# 2uprava4.net
KiCad netlist of a schematic drawn in EAGLE
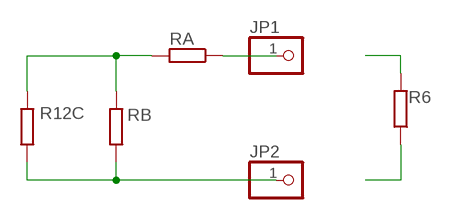
[diagram p0: schematic, sheet 1]

(export (version "E")
  (design (tool "Eeschema 10.0.6"))
  (components
    (comp (ref "JP1")
      (value "PINHD-1X1")
      (footprint "eagle-import:1X01")
      (libsource (lib "eagle-import") (part "PINHD-1X1"))
    )
    (comp (ref "JP2")
      (value "PINHD-1X1")
      (footprint "eagle-import:1X01")
      (libsource (lib "eagle-import") (part "PINHD-1X1"))
    )
    (comp (ref "R6")
      (value "200R")
      (footprint "eagle-import:0204_7")
      (libsource (lib "eagle-import") (part "R-EU_0204/7"))
    )
    (comp (ref "R12C")
      (value "220R")
      (footprint "eagle-import:0204_7")
      (libsource (lib "eagle-import") (part "R-EU_0204/7"))
    )
    (comp (ref "RA")
      (value "570R")
      (footprint "eagle-import:0204_7")
      (libsource (lib "eagle-import") (part "R-EU_0204/7"))
    )
    (comp (ref "RB")
      (value "610R")
      (footprint "eagle-import:0204_7")
      (libsource (lib "eagle-import") (part "R-EU_0204/7"))
    )
  )
  (nets
    (net (code "1") (name "Net-(JP1-Pad1)") (class "Default")
      (node (ref "JP1") (pin "1") (pinfunction "1_1") (pintype "passive"))
      (node (ref "RA") (pin "1") (pinfunction "1_1") (pintype "passive"))
    )
    (net (code "2") (name "Net-(JP2-Pad1)") (class "Default")
      (node (ref "JP2") (pin "1") (pinfunction "1_1") (pintype "passive"))
      (node (ref "R12C") (pin "1") (pinfunction "1_1") (pintype "passive"))
      (node (ref "RB") (pin "1") (pinfunction "1_1") (pintype "passive"))
    )
    (net (code "3") (name "Net-(R12C-Pad2)") (class "Default")
      (node (ref "R12C") (pin "2") (pinfunction "2_2") (pintype "passive"))
      (node (ref "RA") (pin "2") (pinfunction "2_2") (pintype "passive"))
      (node (ref "RB") (pin "2") (pinfunction "2_2") (pintype "passive"))
    )
    (net (code "4") (name "unconnected-(R6-Pad1)") (class "Default")
      (node (ref "R6") (pin "1") (pinfunction "1_1") (pintype "passive"))
    )
    (net (code "5") (name "unconnected-(R6-Pad2)") (class "Default")
      (node (ref "R6") (pin "2") (pinfunction "2_2") (pintype "passive"))
    )
  )
)
